# valiant_v3.net
KiCad netlist of a schematic drawn in EAGLE
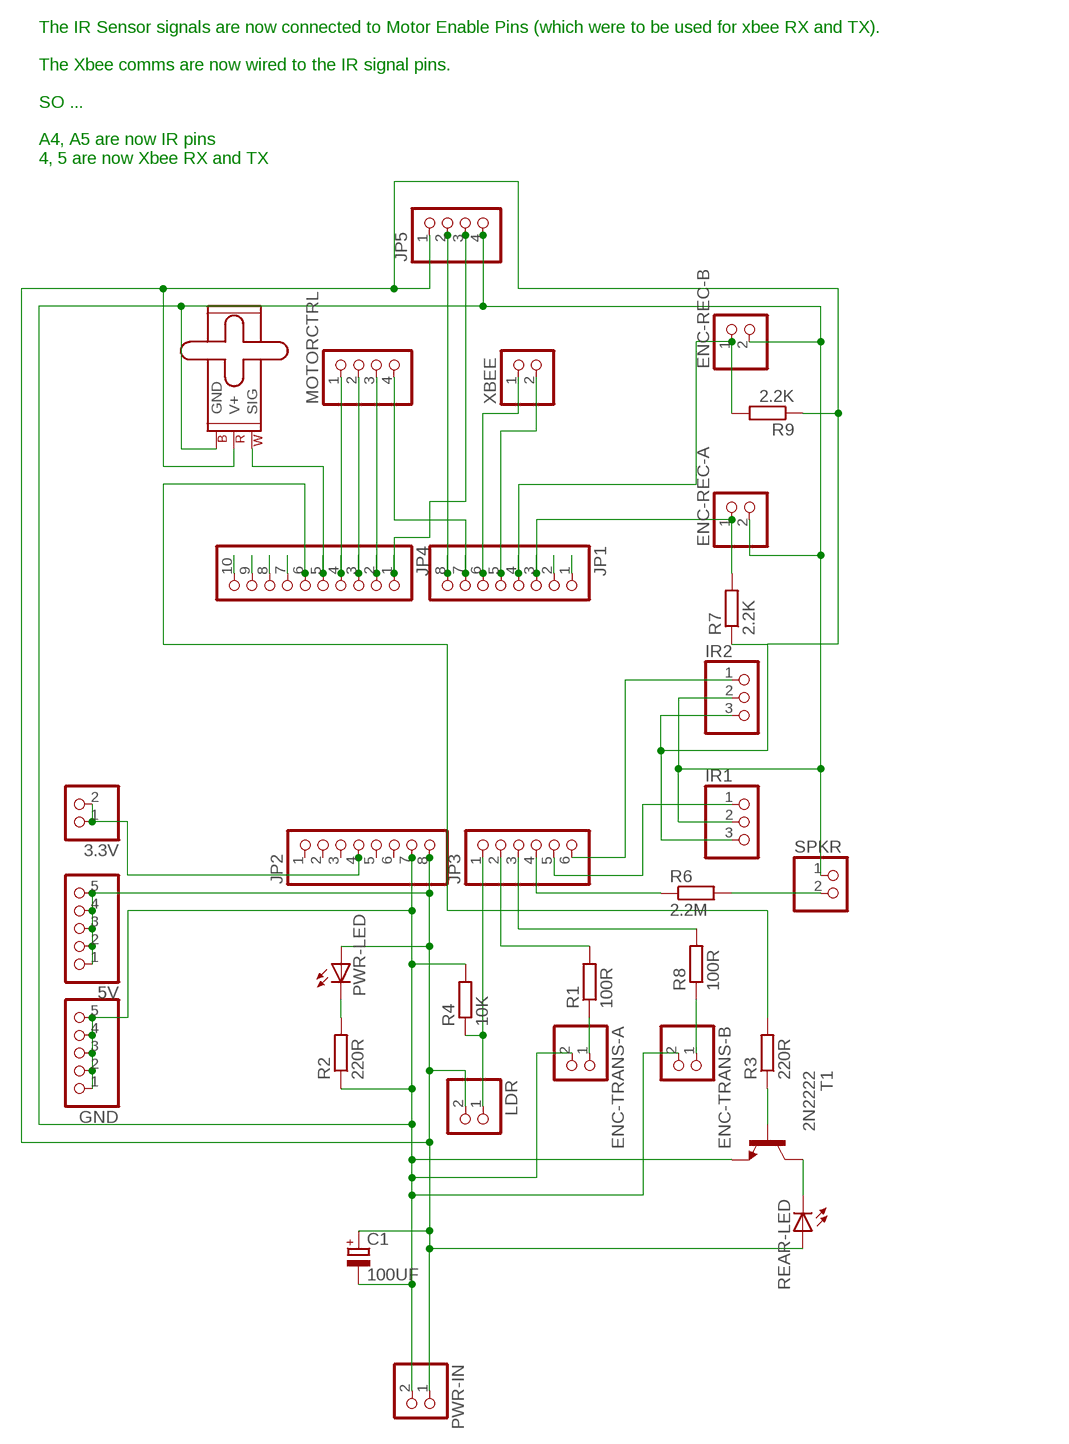
[diagram p0: schematic, sheet 1]

(export (version "E")
  (design (tool "Eeschema 10.0.6"))
  (components
    (comp (ref "3.3V")
      (value "PINHD-1X2")
      (footprint "eagle-import:1X02")
      (libsource (lib "eagle-import") (part "PINHD-1X2"))
    )
    (comp (ref "5V")
      (value "PINHD-1X5")
      (footprint "eagle-import:1X05")
      (libsource (lib "eagle-import") (part "PINHD-1X5"))
    )
    (comp (ref "C1")
      (value "100UF")
      (footprint "eagle-import:E2,5-6E")
      (libsource (lib "eagle-import") (part "CPOL-EUE2,5-6E"))
    )
    (comp (ref "ENC-REC-A")
      (value "PINHD-1X2")
      (footprint "eagle-import:1X02")
      (libsource (lib "eagle-import") (part "PINHD-1X2"))
    )
    (comp (ref "ENC-REC-B")
      (value "PINHD-1X2")
      (footprint "eagle-import:1X02")
      (libsource (lib "eagle-import") (part "PINHD-1X2"))
    )
    (comp (ref "ENC-TRANS-A")
      (value "PINHD-1X2")
      (footprint "eagle-import:1X02")
      (libsource (lib "eagle-import") (part "PINHD-1X2"))
    )
    (comp (ref "ENC-TRANS-B")
      (value "PINHD-1X2")
      (footprint "eagle-import:1X02")
      (libsource (lib "eagle-import") (part "PINHD-1X2"))
    )
    (comp (ref "GND")
      (value "PINHD-1X5")
      (footprint "eagle-import:1X05")
      (libsource (lib "eagle-import") (part "PINHD-1X5"))
    )
    (comp (ref "IR1")
      (value "PINHD-1X3")
      (footprint "eagle-import:1X03")
      (libsource (lib "eagle-import") (part "PINHD-1X3"))
    )
    (comp (ref "IR2")
      (value "PINHD-1X3")
      (footprint "eagle-import:1X03")
      (libsource (lib "eagle-import") (part "PINHD-1X3"))
    )
    (comp (ref "JP1")
      (value "PINHD-1X8")
      (footprint "eagle-import:1X08")
      (libsource (lib "eagle-import") (part "PINHD-1X8"))
    )
    (comp (ref "JP2")
      (value "PINHD-1X8")
      (footprint "eagle-import:1X08")
      (libsource (lib "eagle-import") (part "PINHD-1X8"))
    )
    (comp (ref "JP3")
      (value "PINHD-1X6")
      (footprint "eagle-import:1X06")
      (libsource (lib "eagle-import") (part "PINHD-1X6"))
    )
    (comp (ref "JP4")
      (value "PINHD-1X10")
      (footprint "eagle-import:1X10")
      (libsource (lib "eagle-import") (part "PINHD-1X10"))
    )
    (comp (ref "JP5")
      (value "PINHD-1X4")
      (footprint "eagle-import:1X04")
      (libsource (lib "eagle-import") (part "PINHD-1X4"))
    )
    (comp (ref "LDR")
      (value "PINHD-1X2")
      (footprint "eagle-import:1X02")
      (libsource (lib "eagle-import") (part "PINHD-1X2"))
    )
    (comp (ref "M1")
      (value "SMALL_SERVO")
      (footprint "eagle-import:1X03")
      (libsource (lib "eagle-import") (part "SMALL_SERVO"))
    )
    (comp (ref "MOTORCTRL")
      (value "PINHD-1X4")
      (footprint "eagle-import:1X04")
      (libsource (lib "eagle-import") (part "PINHD-1X4"))
    )
    (comp (ref "PWR-IN")
      (value "PINHD-1X2")
      (footprint "eagle-import:1X02")
      (libsource (lib "eagle-import") (part "PINHD-1X2"))
    )
    (comp (ref "PWR-LED")
      (value "LED5MM")
      (footprint "eagle-import:LED5MM")
      (libsource (lib "eagle-import") (part "LED5MM"))
    )
    (comp (ref "R1")
      (value "100R")
      (footprint "eagle-import:0204_7")
      (libsource (lib "eagle-import") (part "R-EU_0204/7"))
    )
    (comp (ref "R2")
      (value "220R")
      (footprint "eagle-import:0204_7")
      (libsource (lib "eagle-import") (part "R-EU_0204/7"))
    )
    (comp (ref "R3")
      (value "220R")
      (footprint "eagle-import:0204_7")
      (libsource (lib "eagle-import") (part "R-EU_0204/7"))
    )
    (comp (ref "R4")
      (value "10K")
      (footprint "eagle-import:0204_7")
      (libsource (lib "eagle-import") (part "R-EU_0204/7"))
    )
    (comp (ref "R6")
      (value "2.2M")
      (footprint "eagle-import:0204_7")
      (libsource (lib "eagle-import") (part "R-EU_0204/7"))
    )
    (comp (ref "R7")
      (value "2.2K")
      (footprint "eagle-import:0204_7")
      (libsource (lib "eagle-import") (part "R-EU_0204/7"))
    )
    (comp (ref "R8")
      (value "100R")
      (footprint "eagle-import:0204_7")
      (libsource (lib "eagle-import") (part "R-EU_0204/7"))
    )
    (comp (ref "R9")
      (value "2.2K")
      (footprint "eagle-import:0204_7")
      (libsource (lib "eagle-import") (part "R-EU_0204/7"))
    )
    (comp (ref "REAR-LED")
      (value "LED5MM")
      (footprint "eagle-import:LED5MM")
      (libsource (lib "eagle-import") (part "LED5MM"))
    )
    (comp (ref "SPKR")
      (value "PINHD-1X2")
      (footprint "eagle-import:1X02")
      (libsource (lib "eagle-import") (part "PINHD-1X2"))
    )
    (comp (ref "T1")
      (value "2N2222")
      (footprint "eagle-import:TO92-EBC-OVAL")
      (libsource (lib "eagle-import") (part "2N2222"))
    )
    (comp (ref "XBEE")
      (value "PINHD-1X2")
      (footprint "eagle-import:1X02")
      (libsource (lib "eagle-import") (part "PINHD-1X2"))
    )
  )
  (nets
    (net (code "1") (name "Net-(3.3V-Pad1)") (class "Default")
      (node (ref "3.3V") (pin "1") (pinfunction "1_1") (pintype "passive"))
      (node (ref "3.3V") (pin "2") (pinfunction "2_2") (pintype "passive"))
      (node (ref "JP2") (pin "4") (pinfunction "4_4") (pintype "passive"))
    )
    (net (code "2") (name "Net-(ENC-REC-A-Pad1)") (class "Default")
      (node (ref "ENC-REC-A") (pin "1") (pinfunction "1_1") (pintype "passive"))
      (node (ref "JP1") (pin "3") (pinfunction "3_3") (pintype "passive"))
      (node (ref "R7") (pin "2") (pinfunction "2_2") (pintype "passive"))
    )
    (net (code "3") (name "Net-(ENC-REC-B-Pad1)") (class "Default")
      (node (ref "ENC-REC-B") (pin "1") (pinfunction "1_1") (pintype "passive"))
      (node (ref "JP1") (pin "4") (pinfunction "4_4") (pintype "passive"))
      (node (ref "R9") (pin "2") (pinfunction "2_2") (pintype "passive"))
    )
    (net (code "4") (name "Net-(ENC-TRANS-A-Pad1)") (class "Default")
      (node (ref "ENC-TRANS-A") (pin "1") (pinfunction "1_1") (pintype "passive"))
      (node (ref "R1") (pin "1") (pinfunction "1_1") (pintype "passive"))
    )
    (net (code "5") (name "Net-(ENC-TRANS-B-Pad1)") (class "Default")
      (node (ref "ENC-TRANS-B") (pin "1") (pinfunction "1_1") (pintype "passive"))
      (node (ref "R8") (pin "1") (pinfunction "1_1") (pintype "passive"))
    )
    (net (code "6") (name "Net-(IR1-Pad1)") (class "Default")
      (node (ref "IR1") (pin "1") (pinfunction "1_1") (pintype "passive"))
      (node (ref "JP3") (pin "5") (pinfunction "5_5") (pintype "passive"))
    )
    (net (code "7") (name "Net-(IR2-Pad1)") (class "Default")
      (node (ref "IR2") (pin "1") (pinfunction "1_1") (pintype "passive"))
      (node (ref "JP3") (pin "6") (pinfunction "6_6") (pintype "passive"))
    )
    (net (code "8") (name "Net-(JP1-Pad5)") (class "Default")
      (node (ref "JP1") (pin "5") (pinfunction "5_5") (pintype "passive"))
      (node (ref "XBEE") (pin "2") (pinfunction "2_2") (pintype "passive"))
    )
    (net (code "9") (name "Net-(JP1-Pad6)") (class "Default")
      (node (ref "JP1") (pin "6") (pinfunction "6_6") (pintype "passive"))
      (node (ref "XBEE") (pin "1") (pinfunction "1_1") (pintype "passive"))
    )
    (net (code "10") (name "Net-(JP1-Pad7)") (class "Default")
      (node (ref "JP1") (pin "7") (pinfunction "7_7") (pintype "passive"))
      (node (ref "MOTORCTRL") (pin "4") (pinfunction "4_4") (pintype "passive"))
    )
    (net (code "11") (name "Net-(JP1-Pad8)") (class "Default")
      (node (ref "JP1") (pin "8") (pinfunction "8_8") (pintype "passive"))
      (node (ref "JP5") (pin "2") (pinfunction "2_2") (pintype "passive"))
    )
    (net (code "12") (name "Net-(JP3-Pad1)") (class "Default")
      (node (ref "JP3") (pin "1") (pinfunction "1_1") (pintype "passive"))
      (node (ref "LDR") (pin "1") (pinfunction "1_1") (pintype "passive"))
      (node (ref "R4") (pin "1") (pinfunction "1_1") (pintype "passive"))
    )
    (net (code "13") (name "Net-(JP3-Pad2)") (class "Default")
      (node (ref "JP3") (pin "2") (pinfunction "2_2") (pintype "passive"))
      (node (ref "R1") (pin "2") (pinfunction "2_2") (pintype "passive"))
    )
    (net (code "14") (name "Net-(JP3-Pad3)") (class "Default")
      (node (ref "JP3") (pin "3") (pinfunction "3_3") (pintype "passive"))
      (node (ref "R8") (pin "2") (pinfunction "2_2") (pintype "passive"))
    )
    (net (code "15") (name "Net-(JP3-Pad4)") (class "Default")
      (node (ref "JP3") (pin "4") (pinfunction "4_4") (pintype "passive"))
      (node (ref "R6") (pin "1") (pinfunction "1_1") (pintype "passive"))
    )
    (net (code "16") (name "Net-(JP4-Pad1)") (class "Default")
      (node (ref "JP4") (pin "1") (pinfunction "1_1") (pintype "passive"))
      (node (ref "JP5") (pin "3") (pinfunction "3_3") (pintype "passive"))
    )
    (net (code "17") (name "Net-(JP4-Pad2)") (class "Default")
      (node (ref "JP4") (pin "2") (pinfunction "2_2") (pintype "passive"))
      (node (ref "MOTORCTRL") (pin "3") (pinfunction "3_3") (pintype "passive"))
    )
    (net (code "18") (name "Net-(JP4-Pad3)") (class "Default")
      (node (ref "JP4") (pin "3") (pinfunction "3_3") (pintype "passive"))
      (node (ref "MOTORCTRL") (pin "2") (pinfunction "2_2") (pintype "passive"))
    )
    (net (code "19") (name "Net-(JP4-Pad4)") (class "Default")
      (node (ref "JP4") (pin "4") (pinfunction "4_4") (pintype "passive"))
      (node (ref "MOTORCTRL") (pin "1") (pinfunction "1_1") (pintype "passive"))
    )
    (net (code "20") (name "Net-(JP4-Pad6)") (class "Default")
      (node (ref "JP4") (pin "6") (pinfunction "6_6") (pintype "passive"))
      (node (ref "R3") (pin "2") (pinfunction "2_2") (pintype "passive"))
    )
    (net (code "21") (name "Net-(M1-GND)") (class "Default")
      (node (ref "C1") (pin "-") (pinfunction "-_-") (pintype "passive"))
      (node (ref "ENC-REC-A") (pin "2") (pinfunction "2_2") (pintype "passive"))
      (node (ref "ENC-REC-B") (pin "2") (pinfunction "2_2") (pintype "passive"))
      (node (ref "ENC-TRANS-A") (pin "2") (pinfunction "2_2") (pintype "passive"))
      (node (ref "ENC-TRANS-B") (pin "2") (pinfunction "2_2") (pintype "passive"))
      (node (ref "GND") (pin "1") (pinfunction "1_1") (pintype "passive"))
      (node (ref "GND") (pin "2") (pinfunction "2_2") (pintype "passive"))
      (node (ref "GND") (pin "3") (pinfunction "3_3") (pintype "passive"))
      (node (ref "GND") (pin "4") (pinfunction "4_4") (pintype "passive"))
      (node (ref "GND") (pin "5") (pinfunction "5_5") (pintype "passive"))
      (node (ref "IR1") (pin "2") (pinfunction "2_2") (pintype "passive"))
      (node (ref "IR2") (pin "2") (pinfunction "2_2") (pintype "passive"))
      (node (ref "JP2") (pin "7") (pinfunction "7_7") (pintype "passive"))
      (node (ref "JP5") (pin "4") (pinfunction "4_4") (pintype "passive"))
      (node (ref "M1") (pin "3") (pinfunction "GND_3") (pintype "bidirectional"))
      (node (ref "PWR-IN") (pin "2") (pinfunction "2_2") (pintype "passive"))
      (node (ref "R2") (pin "1") (pinfunction "1_1") (pintype "passive"))
      (node (ref "R4") (pin "2") (pinfunction "2_2") (pintype "passive"))
      (node (ref "SPKR") (pin "1") (pinfunction "1_1") (pintype "passive"))
      (node (ref "T1") (pin "E") (pinfunction "E_E") (pintype "passive"))
    )
    (net (code "22") (name "Net-(M1-SIG)") (class "Default")
      (node (ref "JP4") (pin "5") (pinfunction "5_5") (pintype "passive"))
      (node (ref "M1") (pin "1") (pinfunction "SIG_1") (pintype "bidirectional"))
    )
    (net (code "23") (name "Net-(M1-V+)") (class "Default")
      (node (ref "5V") (pin "1") (pinfunction "1_1") (pintype "passive"))
      (node (ref "5V") (pin "2") (pinfunction "2_2") (pintype "passive"))
      (node (ref "5V") (pin "3") (pinfunction "3_3") (pintype "passive"))
      (node (ref "5V") (pin "4") (pinfunction "4_4") (pintype "passive"))
      (node (ref "5V") (pin "5") (pinfunction "5_5") (pintype "passive"))
      (node (ref "C1") (pin "+") (pinfunction "+_+") (pintype "passive"))
      (node (ref "IR1") (pin "3") (pinfunction "3_3") (pintype "passive"))
      (node (ref "IR2") (pin "3") (pinfunction "3_3") (pintype "passive"))
      (node (ref "JP2") (pin "8") (pinfunction "8_8") (pintype "passive"))
      (node (ref "JP5") (pin "1") (pinfunction "1_1") (pintype "passive"))
      (node (ref "LDR") (pin "2") (pinfunction "2_2") (pintype "passive"))
      (node (ref "M1") (pin "2") (pinfunction "V+_2") (pintype "bidirectional"))
      (node (ref "PWR-IN") (pin "1") (pinfunction "1_1") (pintype "passive"))
      (node (ref "PWR-LED") (pin "A") (pinfunction "A_A") (pintype "passive"))
      (node (ref "R7") (pin "1") (pinfunction "1_1") (pintype "passive"))
      (node (ref "R9") (pin "1") (pinfunction "1_1") (pintype "passive"))
      (node (ref "REAR-LED") (pin "A") (pinfunction "A_A") (pintype "passive"))
    )
    (net (code "24") (name "Net-(PWR-LED-C)") (class "Default")
      (node (ref "PWR-LED") (pin "K") (pinfunction "C_K") (pintype "passive"))
      (node (ref "R2") (pin "2") (pinfunction "2_2") (pintype "passive"))
    )
    (net (code "25") (name "Net-(R3-Pad1)") (class "Default")
      (node (ref "R3") (pin "1") (pinfunction "1_1") (pintype "passive"))
      (node (ref "T1") (pin "B") (pinfunction "B_B") (pintype "passive"))
    )
    (net (code "26") (name "Net-(R6-Pad2)") (class "Default")
      (node (ref "R6") (pin "2") (pinfunction "2_2") (pintype "passive"))
      (node (ref "SPKR") (pin "2") (pinfunction "2_2") (pintype "passive"))
    )
    (net (code "27") (name "Net-(REAR-LED-C)") (class "Default")
      (node (ref "REAR-LED") (pin "K") (pinfunction "C_K") (pintype "passive"))
      (node (ref "T1") (pin "C") (pinfunction "C_C") (pintype "passive"))
    )
    (net (code "28") (name "unconnected-(JP1-Pad1)") (class "Default")
      (node (ref "JP1") (pin "1") (pinfunction "1_1") (pintype "passive"))
    )
    (net (code "29") (name "unconnected-(JP1-Pad2)") (class "Default")
      (node (ref "JP1") (pin "2") (pinfunction "2_2") (pintype "passive"))
    )
    (net (code "30") (name "unconnected-(JP2-Pad1)") (class "Default")
      (node (ref "JP2") (pin "1") (pinfunction "1_1") (pintype "passive"))
    )
    (net (code "31") (name "unconnected-(JP2-Pad2)") (class "Default")
      (node (ref "JP2") (pin "2") (pinfunction "2_2") (pintype "passive"))
    )
    (net (code "32") (name "unconnected-(JP2-Pad3)") (class "Default")
      (node (ref "JP2") (pin "3") (pinfunction "3_3") (pintype "passive"))
    )
    (net (code "33") (name "unconnected-(JP2-Pad5)") (class "Default")
      (node (ref "JP2") (pin "5") (pinfunction "5_5") (pintype "passive"))
    )
    (net (code "34") (name "unconnected-(JP2-Pad6)") (class "Default")
      (node (ref "JP2") (pin "6") (pinfunction "6_6") (pintype "passive"))
    )
    (net (code "35") (name "unconnected-(JP4-Pad7)") (class "Default")
      (node (ref "JP4") (pin "7") (pinfunction "7_7") (pintype "passive"))
    )
    (net (code "36") (name "unconnected-(JP4-Pad8)") (class "Default")
      (node (ref "JP4") (pin "8") (pinfunction "8_8") (pintype "passive"))
    )
    (net (code "37") (name "unconnected-(JP4-Pad9)") (class "Default")
      (node (ref "JP4") (pin "9") (pinfunction "9_9") (pintype "passive"))
    )
    (net (code "38") (name "unconnected-(JP4-Pad10)") (class "Default")
      (node (ref "JP4") (pin "10") (pinfunction "10_10") (pintype "passive"))
    )
  )
)
